# Electrical_main_panel.net
KiCad netlist of a schematic drawn in EAGLE
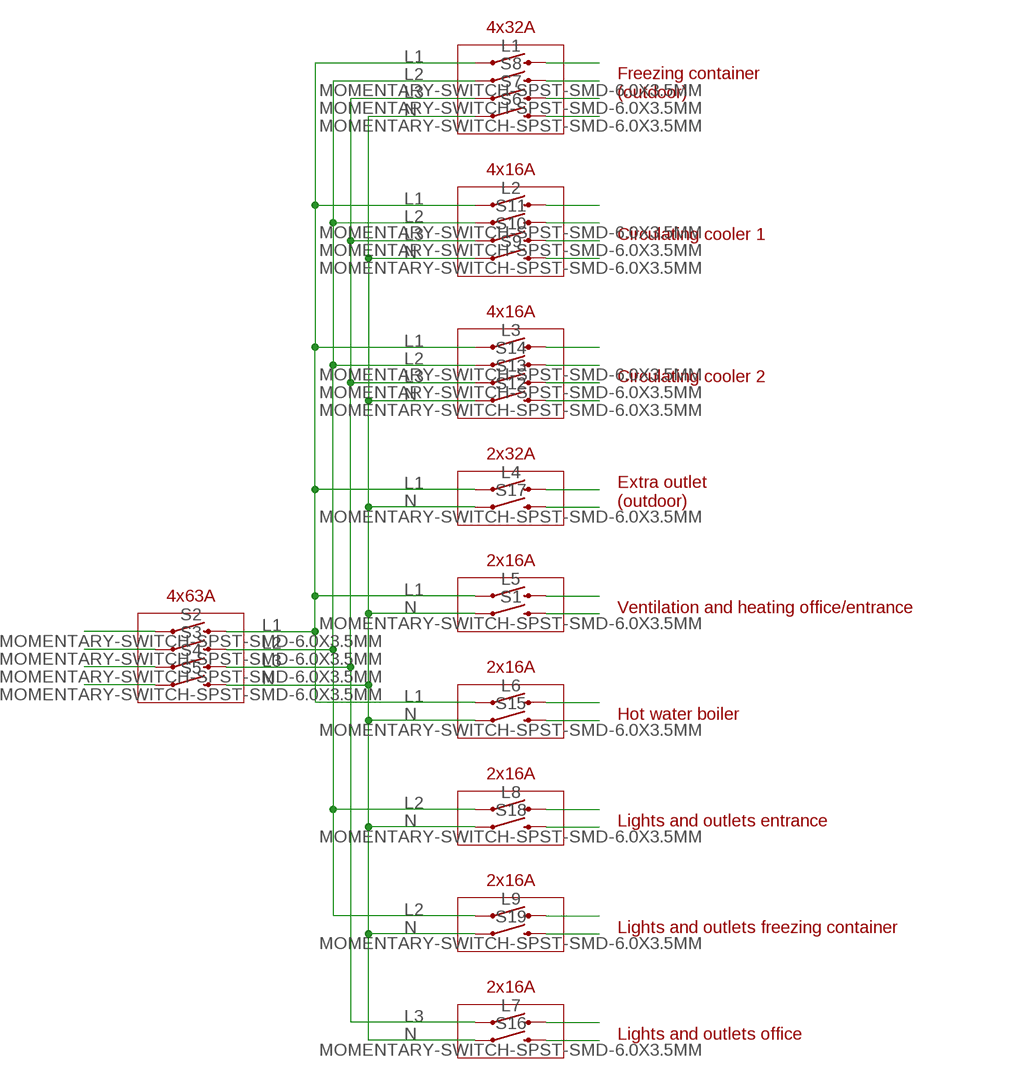
[diagram p0: schematic, sheet 1]

(export (version "E")
  (design (tool "Eeschema 10.0.6"))
  (components
    (comp (ref "L1")
      (value "MOMENTARY-SWITCH-SPST-SMD-6.0X3.5MM")
      (footprint "eagle-import:TACTILE_SWITCH_SMD_6.0X3.5MM")
      (libsource (lib "eagle-import") (part "MOMENTARY-SWITCH-SPST-SMD-6.0X3.5MM"))
    )
    (comp (ref "L2")
      (value "MOMENTARY-SWITCH-SPST-SMD-6.0X3.5MM")
      (footprint "eagle-import:TACTILE_SWITCH_SMD_6.0X3.5MM")
      (libsource (lib "eagle-import") (part "MOMENTARY-SWITCH-SPST-SMD-6.0X3.5MM"))
    )
    (comp (ref "L3")
      (value "MOMENTARY-SWITCH-SPST-SMD-6.0X3.5MM")
      (footprint "eagle-import:TACTILE_SWITCH_SMD_6.0X3.5MM")
      (libsource (lib "eagle-import") (part "MOMENTARY-SWITCH-SPST-SMD-6.0X3.5MM"))
    )
    (comp (ref "L4")
      (value "MOMENTARY-SWITCH-SPST-SMD-6.0X3.5MM")
      (footprint "eagle-import:TACTILE_SWITCH_SMD_6.0X3.5MM")
      (libsource (lib "eagle-import") (part "MOMENTARY-SWITCH-SPST-SMD-6.0X3.5MM"))
    )
    (comp (ref "L5")
      (value "MOMENTARY-SWITCH-SPST-SMD-6.0X3.5MM")
      (footprint "eagle-import:TACTILE_SWITCH_SMD_6.0X3.5MM")
      (libsource (lib "eagle-import") (part "MOMENTARY-SWITCH-SPST-SMD-6.0X3.5MM"))
    )
    (comp (ref "L6")
      (value "MOMENTARY-SWITCH-SPST-SMD-6.0X3.5MM")
      (footprint "eagle-import:TACTILE_SWITCH_SMD_6.0X3.5MM")
      (libsource (lib "eagle-import") (part "MOMENTARY-SWITCH-SPST-SMD-6.0X3.5MM"))
    )
    (comp (ref "L7")
      (value "MOMENTARY-SWITCH-SPST-SMD-6.0X3.5MM")
      (footprint "eagle-import:TACTILE_SWITCH_SMD_6.0X3.5MM")
      (libsource (lib "eagle-import") (part "MOMENTARY-SWITCH-SPST-SMD-6.0X3.5MM"))
    )
    (comp (ref "L8")
      (value "MOMENTARY-SWITCH-SPST-SMD-6.0X3.5MM")
      (footprint "eagle-import:TACTILE_SWITCH_SMD_6.0X3.5MM")
      (libsource (lib "eagle-import") (part "MOMENTARY-SWITCH-SPST-SMD-6.0X3.5MM"))
    )
    (comp (ref "L9")
      (value "MOMENTARY-SWITCH-SPST-SMD-6.0X3.5MM")
      (footprint "eagle-import:TACTILE_SWITCH_SMD_6.0X3.5MM")
      (libsource (lib "eagle-import") (part "MOMENTARY-SWITCH-SPST-SMD-6.0X3.5MM"))
    )
    (comp (ref "S1")
      (value "MOMENTARY-SWITCH-SPST-SMD-6.0X3.5MM")
      (footprint "eagle-import:TACTILE_SWITCH_SMD_6.0X3.5MM")
      (libsource (lib "eagle-import") (part "MOMENTARY-SWITCH-SPST-SMD-6.0X3.5MM"))
    )
    (comp (ref "S2")
      (value "MOMENTARY-SWITCH-SPST-SMD-6.0X3.5MM")
      (footprint "eagle-import:TACTILE_SWITCH_SMD_6.0X3.5MM")
      (libsource (lib "eagle-import") (part "MOMENTARY-SWITCH-SPST-SMD-6.0X3.5MM"))
    )
    (comp (ref "S3")
      (value "MOMENTARY-SWITCH-SPST-SMD-6.0X3.5MM")
      (footprint "eagle-import:TACTILE_SWITCH_SMD_6.0X3.5MM")
      (libsource (lib "eagle-import") (part "MOMENTARY-SWITCH-SPST-SMD-6.0X3.5MM"))
    )
    (comp (ref "S4")
      (value "MOMENTARY-SWITCH-SPST-SMD-6.0X3.5MM")
      (footprint "eagle-import:TACTILE_SWITCH_SMD_6.0X3.5MM")
      (libsource (lib "eagle-import") (part "MOMENTARY-SWITCH-SPST-SMD-6.0X3.5MM"))
    )
    (comp (ref "S5")
      (value "MOMENTARY-SWITCH-SPST-SMD-6.0X3.5MM")
      (footprint "eagle-import:TACTILE_SWITCH_SMD_6.0X3.5MM")
      (libsource (lib "eagle-import") (part "MOMENTARY-SWITCH-SPST-SMD-6.0X3.5MM"))
    )
    (comp (ref "S6")
      (value "MOMENTARY-SWITCH-SPST-SMD-6.0X3.5MM")
      (footprint "eagle-import:TACTILE_SWITCH_SMD_6.0X3.5MM")
      (libsource (lib "eagle-import") (part "MOMENTARY-SWITCH-SPST-SMD-6.0X3.5MM"))
    )
    (comp (ref "S7")
      (value "MOMENTARY-SWITCH-SPST-SMD-6.0X3.5MM")
      (footprint "eagle-import:TACTILE_SWITCH_SMD_6.0X3.5MM")
      (libsource (lib "eagle-import") (part "MOMENTARY-SWITCH-SPST-SMD-6.0X3.5MM"))
    )
    (comp (ref "S8")
      (value "MOMENTARY-SWITCH-SPST-SMD-6.0X3.5MM")
      (footprint "eagle-import:TACTILE_SWITCH_SMD_6.0X3.5MM")
      (libsource (lib "eagle-import") (part "MOMENTARY-SWITCH-SPST-SMD-6.0X3.5MM"))
    )
    (comp (ref "S9")
      (value "MOMENTARY-SWITCH-SPST-SMD-6.0X3.5MM")
      (footprint "eagle-import:TACTILE_SWITCH_SMD_6.0X3.5MM")
      (libsource (lib "eagle-import") (part "MOMENTARY-SWITCH-SPST-SMD-6.0X3.5MM"))
    )
    (comp (ref "S10")
      (value "MOMENTARY-SWITCH-SPST-SMD-6.0X3.5MM")
      (footprint "eagle-import:TACTILE_SWITCH_SMD_6.0X3.5MM")
      (libsource (lib "eagle-import") (part "MOMENTARY-SWITCH-SPST-SMD-6.0X3.5MM"))
    )
    (comp (ref "S11")
      (value "MOMENTARY-SWITCH-SPST-SMD-6.0X3.5MM")
      (footprint "eagle-import:TACTILE_SWITCH_SMD_6.0X3.5MM")
      (libsource (lib "eagle-import") (part "MOMENTARY-SWITCH-SPST-SMD-6.0X3.5MM"))
    )
    (comp (ref "S12")
      (value "MOMENTARY-SWITCH-SPST-SMD-6.0X3.5MM")
      (footprint "eagle-import:TACTILE_SWITCH_SMD_6.0X3.5MM")
      (libsource (lib "eagle-import") (part "MOMENTARY-SWITCH-SPST-SMD-6.0X3.5MM"))
    )
    (comp (ref "S13")
      (value "MOMENTARY-SWITCH-SPST-SMD-6.0X3.5MM")
      (footprint "eagle-import:TACTILE_SWITCH_SMD_6.0X3.5MM")
      (libsource (lib "eagle-import") (part "MOMENTARY-SWITCH-SPST-SMD-6.0X3.5MM"))
    )
    (comp (ref "S14")
      (value "MOMENTARY-SWITCH-SPST-SMD-6.0X3.5MM")
      (footprint "eagle-import:TACTILE_SWITCH_SMD_6.0X3.5MM")
      (libsource (lib "eagle-import") (part "MOMENTARY-SWITCH-SPST-SMD-6.0X3.5MM"))
    )
    (comp (ref "S15")
      (value "MOMENTARY-SWITCH-SPST-SMD-6.0X3.5MM")
      (footprint "eagle-import:TACTILE_SWITCH_SMD_6.0X3.5MM")
      (libsource (lib "eagle-import") (part "MOMENTARY-SWITCH-SPST-SMD-6.0X3.5MM"))
    )
    (comp (ref "S16")
      (value "MOMENTARY-SWITCH-SPST-SMD-6.0X3.5MM")
      (footprint "eagle-import:TACTILE_SWITCH_SMD_6.0X3.5MM")
      (libsource (lib "eagle-import") (part "MOMENTARY-SWITCH-SPST-SMD-6.0X3.5MM"))
    )
    (comp (ref "S17")
      (value "MOMENTARY-SWITCH-SPST-SMD-6.0X3.5MM")
      (footprint "eagle-import:TACTILE_SWITCH_SMD_6.0X3.5MM")
      (libsource (lib "eagle-import") (part "MOMENTARY-SWITCH-SPST-SMD-6.0X3.5MM"))
    )
    (comp (ref "S18")
      (value "MOMENTARY-SWITCH-SPST-SMD-6.0X3.5MM")
      (footprint "eagle-import:TACTILE_SWITCH_SMD_6.0X3.5MM")
      (libsource (lib "eagle-import") (part "MOMENTARY-SWITCH-SPST-SMD-6.0X3.5MM"))
    )
    (comp (ref "S19")
      (value "MOMENTARY-SWITCH-SPST-SMD-6.0X3.5MM")
      (footprint "eagle-import:TACTILE_SWITCH_SMD_6.0X3.5MM")
      (libsource (lib "eagle-import") (part "MOMENTARY-SWITCH-SPST-SMD-6.0X3.5MM"))
    )
  )
  (nets
    (net (code "1") (name "/L1") (class "Default")
      (node (ref "L1") (pin "1") (pinfunction "1_1") (pintype "passive"))
      (node (ref "L2") (pin "1") (pinfunction "1_1") (pintype "passive"))
      (node (ref "L3") (pin "1") (pinfunction "1_1") (pintype "passive"))
      (node (ref "L4") (pin "1") (pinfunction "1_1") (pintype "passive"))
      (node (ref "L5") (pin "1") (pinfunction "1_1") (pintype "passive"))
      (node (ref "L6") (pin "1") (pinfunction "1_1") (pintype "passive"))
      (node (ref "S2") (pin "2") (pinfunction "2_2") (pintype "passive"))
    )
    (net (code "2") (name "/L2") (class "Default")
      (node (ref "L8") (pin "1") (pinfunction "1_1") (pintype "passive"))
      (node (ref "L9") (pin "1") (pinfunction "1_1") (pintype "passive"))
      (node (ref "S11") (pin "1") (pinfunction "1_1") (pintype "passive"))
      (node (ref "S14") (pin "1") (pinfunction "1_1") (pintype "passive"))
      (node (ref "S3") (pin "2") (pinfunction "2_2") (pintype "passive"))
      (node (ref "S8") (pin "1") (pinfunction "1_1") (pintype "passive"))
    )
    (net (code "3") (name "/L3") (class "Default")
      (node (ref "L7") (pin "1") (pinfunction "1_1") (pintype "passive"))
      (node (ref "S10") (pin "1") (pinfunction "1_1") (pintype "passive"))
      (node (ref "S13") (pin "1") (pinfunction "1_1") (pintype "passive"))
      (node (ref "S4") (pin "2") (pinfunction "2_2") (pintype "passive"))
      (node (ref "S7") (pin "1") (pinfunction "1_1") (pintype "passive"))
    )
    (net (code "4") (name "/N") (class "Default")
      (node (ref "S1") (pin "1") (pinfunction "1_1") (pintype "passive"))
      (node (ref "S12") (pin "1") (pinfunction "1_1") (pintype "passive"))
      (node (ref "S15") (pin "1") (pinfunction "1_1") (pintype "passive"))
      (node (ref "S16") (pin "1") (pinfunction "1_1") (pintype "passive"))
      (node (ref "S17") (pin "1") (pinfunction "1_1") (pintype "passive"))
      (node (ref "S18") (pin "1") (pinfunction "1_1") (pintype "passive"))
      (node (ref "S19") (pin "1") (pinfunction "1_1") (pintype "passive"))
      (node (ref "S5") (pin "2") (pinfunction "2_2") (pintype "passive"))
      (node (ref "S6") (pin "1") (pinfunction "1_1") (pintype "passive"))
      (node (ref "S9") (pin "1") (pinfunction "1_1") (pintype "passive"))
    )
    (net (code "5") (name "unconnected-(L1-Pad2)") (class "Default")
      (node (ref "L1") (pin "2") (pinfunction "2_2") (pintype "passive"))
    )
    (net (code "6") (name "unconnected-(L2-Pad2)") (class "Default")
      (node (ref "L2") (pin "2") (pinfunction "2_2") (pintype "passive"))
    )
    (net (code "7") (name "unconnected-(L3-Pad2)") (class "Default")
      (node (ref "L3") (pin "2") (pinfunction "2_2") (pintype "passive"))
    )
    (net (code "8") (name "unconnected-(L4-Pad2)") (class "Default")
      (node (ref "L4") (pin "2") (pinfunction "2_2") (pintype "passive"))
    )
    (net (code "9") (name "unconnected-(L5-Pad2)") (class "Default")
      (node (ref "L5") (pin "2") (pinfunction "2_2") (pintype "passive"))
    )
    (net (code "10") (name "unconnected-(L6-Pad2)") (class "Default")
      (node (ref "L6") (pin "2") (pinfunction "2_2") (pintype "passive"))
    )
    (net (code "11") (name "unconnected-(L7-Pad2)") (class "Default")
      (node (ref "L7") (pin "2") (pinfunction "2_2") (pintype "passive"))
    )
    (net (code "12") (name "unconnected-(L8-Pad2)") (class "Default")
      (node (ref "L8") (pin "2") (pinfunction "2_2") (pintype "passive"))
    )
    (net (code "13") (name "unconnected-(L9-Pad2)") (class "Default")
      (node (ref "L9") (pin "2") (pinfunction "2_2") (pintype "passive"))
    )
    (net (code "14") (name "unconnected-(S1-Pad2)") (class "Default")
      (node (ref "S1") (pin "2") (pinfunction "2_2") (pintype "passive"))
    )
    (net (code "15") (name "unconnected-(S2-Pad1)") (class "Default")
      (node (ref "S2") (pin "1") (pinfunction "1_1") (pintype "passive"))
    )
    (net (code "16") (name "unconnected-(S3-Pad1)") (class "Default")
      (node (ref "S3") (pin "1") (pinfunction "1_1") (pintype "passive"))
    )
    (net (code "17") (name "unconnected-(S4-Pad1)") (class "Default")
      (node (ref "S4") (pin "1") (pinfunction "1_1") (pintype "passive"))
    )
    (net (code "18") (name "unconnected-(S5-Pad1)") (class "Default")
      (node (ref "S5") (pin "1") (pinfunction "1_1") (pintype "passive"))
    )
    (net (code "19") (name "unconnected-(S6-Pad2)") (class "Default")
      (node (ref "S6") (pin "2") (pinfunction "2_2") (pintype "passive"))
    )
    (net (code "20") (name "unconnected-(S7-Pad2)") (class "Default")
      (node (ref "S7") (pin "2") (pinfunction "2_2") (pintype "passive"))
    )
    (net (code "21") (name "unconnected-(S8-Pad2)") (class "Default")
      (node (ref "S8") (pin "2") (pinfunction "2_2") (pintype "passive"))
    )
    (net (code "22") (name "unconnected-(S9-Pad2)") (class "Default")
      (node (ref "S9") (pin "2") (pinfunction "2_2") (pintype "passive"))
    )
    (net (code "23") (name "unconnected-(S10-Pad2)") (class "Default")
      (node (ref "S10") (pin "2") (pinfunction "2_2") (pintype "passive"))
    )
    (net (code "24") (name "unconnected-(S11-Pad2)") (class "Default")
      (node (ref "S11") (pin "2") (pinfunction "2_2") (pintype "passive"))
    )
    (net (code "25") (name "unconnected-(S12-Pad2)") (class "Default")
      (node (ref "S12") (pin "2") (pinfunction "2_2") (pintype "passive"))
    )
    (net (code "26") (name "unconnected-(S13-Pad2)") (class "Default")
      (node (ref "S13") (pin "2") (pinfunction "2_2") (pintype "passive"))
    )
    (net (code "27") (name "unconnected-(S14-Pad2)") (class "Default")
      (node (ref "S14") (pin "2") (pinfunction "2_2") (pintype "passive"))
    )
    (net (code "28") (name "unconnected-(S15-Pad2)") (class "Default")
      (node (ref "S15") (pin "2") (pinfunction "2_2") (pintype "passive"))
    )
    (net (code "29") (name "unconnected-(S16-Pad2)") (class "Default")
      (node (ref "S16") (pin "2") (pinfunction "2_2") (pintype "passive"))
    )
    (net (code "30") (name "unconnected-(S17-Pad2)") (class "Default")
      (node (ref "S17") (pin "2") (pinfunction "2_2") (pintype "passive"))
    )
    (net (code "31") (name "unconnected-(S18-Pad2)") (class "Default")
      (node (ref "S18") (pin "2") (pinfunction "2_2") (pintype "passive"))
    )
    (net (code "32") (name "unconnected-(S19-Pad2)") (class "Default")
      (node (ref "S19") (pin "2") (pinfunction "2_2") (pintype "passive"))
    )
  )
)
